# AV_Board.net
KiCad netlist of a schematic drawn in EAGLE
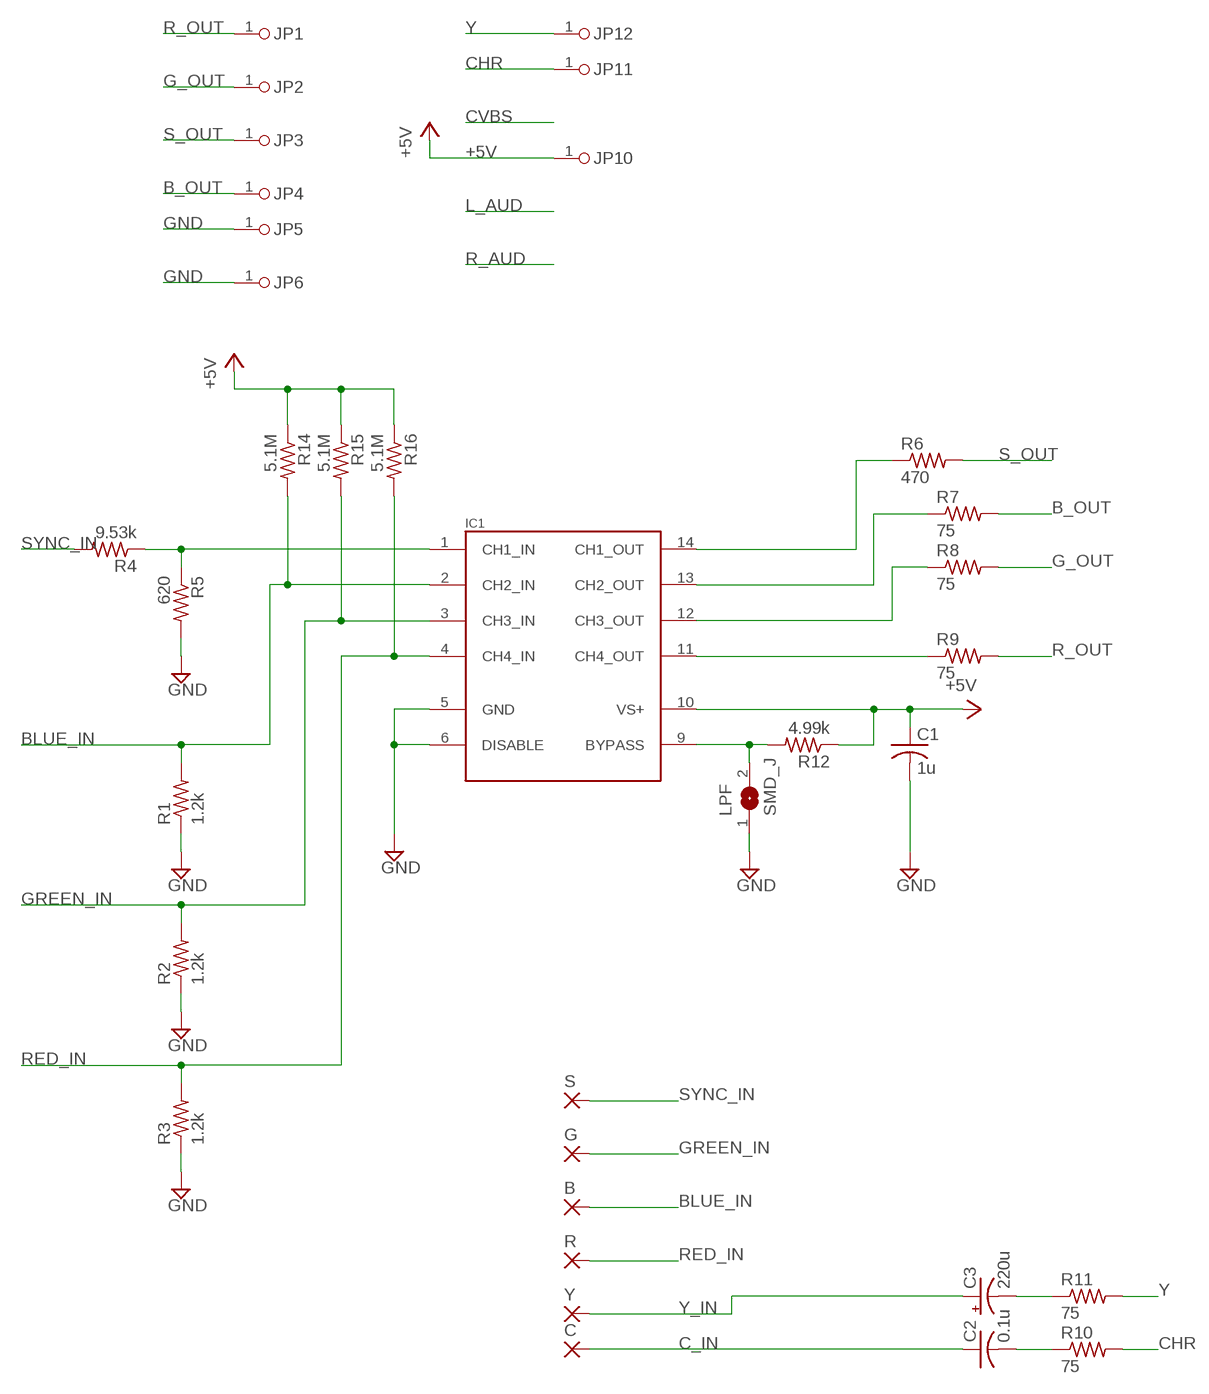
[diagram p0: schematic, sheet 1]

(export (version "E")
  (design (tool "Eeschema 10.0.6"))
  (components
    (comp (ref "B")
      (value "SMD2")
      (footprint "eagle-import:SMD1,27-2,54")
      (libsource (lib "eagle-import") (part "SMD2"))
    )
    (comp (ref "C")
      (value "SMD2")
      (footprint "eagle-import:SMD1,27-2,54")
      (libsource (lib "eagle-import") (part "SMD2"))
    )
    (comp (ref "C1")
      (value "1u")
      (footprint "eagle-import:C0603")
      (libsource (lib "eagle-import") (part "C-USC0603"))
    )
    (comp (ref "C2")
      (value "0.1u")
      (footprint "eagle-import:C0603")
      (libsource (lib "eagle-import") (part "C-USC0603"))
    )
    (comp (ref "C3")
      (value "220u")
      (footprint "eagle-import:CT6032")
      (libsource (lib "eagle-import") (part "CPOL-USCT6032"))
    )
    (comp (ref "G")
      (value "SMD2")
      (footprint "eagle-import:SMD1,27-2,54")
      (libsource (lib "eagle-import") (part "SMD2"))
    )
    (comp (ref "IC1")
      (value "THS7374IPWR")
      (footprint "eagle-import:TSSOP14")
      (libsource (lib "eagle-import") (part "THS7374IPWR"))
    )
    (comp (ref "JP1")
      (value "PINHD-1X1")
      (footprint "eagle-import:1X01")
      (libsource (lib "eagle-import") (part "PINHD-1X1"))
    )
    (comp (ref "JP2")
      (value "PINHD-1X1")
      (footprint "eagle-import:1X01")
      (libsource (lib "eagle-import") (part "PINHD-1X1"))
    )
    (comp (ref "JP3")
      (value "PINHD-1X1")
      (footprint "eagle-import:1X01")
      (libsource (lib "eagle-import") (part "PINHD-1X1"))
    )
    (comp (ref "JP4")
      (value "PINHD-1X1")
      (footprint "eagle-import:1X01")
      (libsource (lib "eagle-import") (part "PINHD-1X1"))
    )
    (comp (ref "JP5")
      (value "PINHD-1X1")
      (footprint "eagle-import:1X01")
      (libsource (lib "eagle-import") (part "PINHD-1X1"))
    )
    (comp (ref "JP6")
      (value "PINHD-1X1")
      (footprint "eagle-import:1X01")
      (libsource (lib "eagle-import") (part "PINHD-1X1"))
    )
    (comp (ref "JP10")
      (value "PINHD-1X1")
      (footprint "eagle-import:1X01")
      (libsource (lib "eagle-import") (part "PINHD-1X1"))
    )
    (comp (ref "JP11")
      (value "PINHD-1X1")
      (footprint "eagle-import:1X01")
      (libsource (lib "eagle-import") (part "PINHD-1X1"))
    )
    (comp (ref "JP12")
      (value "PINHD-1X1")
      (footprint "eagle-import:1X01")
      (libsource (lib "eagle-import") (part "PINHD-1X1"))
    )
    (comp (ref "LPF")
      (value "SMD_J")
      (footprint "eagle-import:SJ")
      (libsource (lib "eagle-import") (part "SMD_J"))
    )
    (comp (ref "R")
      (value "SMD2")
      (footprint "eagle-import:SMD1,27-2,54")
      (libsource (lib "eagle-import") (part "SMD2"))
    )
    (comp (ref "R1")
      (value "1.2k")
      (footprint "eagle-import:R0603")
      (libsource (lib "eagle-import") (part "R-US_R0603"))
    )
    (comp (ref "R2")
      (value "1.2k")
      (footprint "eagle-import:R0603")
      (libsource (lib "eagle-import") (part "R-US_R0603"))
    )
    (comp (ref "R3")
      (value "1.2k")
      (footprint "eagle-import:R0603")
      (libsource (lib "eagle-import") (part "R-US_R0603"))
    )
    (comp (ref "R4")
      (value "9.53k")
      (footprint "eagle-import:R0603")
      (libsource (lib "eagle-import") (part "R-US_R0603"))
    )
    (comp (ref "R5")
      (value "620")
      (footprint "eagle-import:R0603")
      (libsource (lib "eagle-import") (part "R-US_R0603"))
    )
    (comp (ref "R6")
      (value "470")
      (footprint "eagle-import:R0603")
      (libsource (lib "eagle-import") (part "R-US_R0603"))
    )
    (comp (ref "R7")
      (value "75")
      (footprint "eagle-import:R0603")
      (libsource (lib "eagle-import") (part "R-US_R0603"))
    )
    (comp (ref "R8")
      (value "75")
      (footprint "eagle-import:R0603")
      (libsource (lib "eagle-import") (part "R-US_R0603"))
    )
    (comp (ref "R9")
      (value "75")
      (footprint "eagle-import:R0603")
      (libsource (lib "eagle-import") (part "R-US_R0603"))
    )
    (comp (ref "R10")
      (value "75")
      (footprint "eagle-import:R0603")
      (libsource (lib "eagle-import") (part "R-US_R0603"))
    )
    (comp (ref "R11")
      (value "75")
      (footprint "eagle-import:R0603")
      (libsource (lib "eagle-import") (part "R-US_R0603"))
    )
    (comp (ref "R12")
      (value "4.99k")
      (footprint "eagle-import:R0603")
      (libsource (lib "eagle-import") (part "R-US_R0603"))
    )
    (comp (ref "R14")
      (value "5.1M")
      (footprint "eagle-import:R0603")
      (libsource (lib "eagle-import") (part "R-US_R0603"))
    )
    (comp (ref "R15")
      (value "5.1M")
      (footprint "eagle-import:R0603")
      (libsource (lib "eagle-import") (part "R-US_R0603"))
    )
    (comp (ref "R16")
      (value "5.1M")
      (footprint "eagle-import:R0603")
      (libsource (lib "eagle-import") (part "R-US_R0603"))
    )
    (comp (ref "S")
      (value "SMD2")
      (footprint "eagle-import:SMD1,27-2,54")
      (libsource (lib "eagle-import") (part "SMD2"))
    )
    (comp (ref "Y")
      (value "SMD2")
      (footprint "eagle-import:SMD1,27-2,54")
      (libsource (lib "eagle-import") (part "SMD2"))
    )
  )
  (nets
    (net (code "1") (name "+5V") (class "Default")
      (node (ref "C1") (pin "1") (pinfunction "1_1") (pintype "passive"))
      (node (ref "IC1") (pin "10") (pinfunction "VS+_10") (pintype "bidirectional"))
      (node (ref "JP10") (pin "1") (pinfunction "1_1") (pintype "passive"))
      (node (ref "R12") (pin "1") (pinfunction "1_1") (pintype "passive"))
      (node (ref "R14") (pin "1") (pinfunction "1_1") (pintype "passive"))
      (node (ref "R15") (pin "1") (pinfunction "1_1") (pintype "passive"))
      (node (ref "R16") (pin "1") (pinfunction "1_1") (pintype "passive"))
    )
    (net (code "2") (name "/BLUE_IN") (class "Default")
      (node (ref "B") (pin "1") (pinfunction "P_1") (pintype "passive"))
      (node (ref "IC1") (pin "2") (pinfunction "CH2_IN_2") (pintype "bidirectional"))
      (node (ref "R1") (pin "2") (pinfunction "2_2") (pintype "passive"))
      (node (ref "R14") (pin "2") (pinfunction "2_2") (pintype "passive"))
    )
    (net (code "3") (name "/B_OUT") (class "Default")
      (node (ref "JP4") (pin "1") (pinfunction "1_1") (pintype "passive"))
      (node (ref "R7") (pin "2") (pinfunction "2_2") (pintype "passive"))
    )
    (net (code "4") (name "/CHR") (class "Default")
      (node (ref "JP11") (pin "1") (pinfunction "1_1") (pintype "passive"))
      (node (ref "R10") (pin "2") (pinfunction "2_2") (pintype "passive"))
    )
    (net (code "6") (name "/C_IN") (class "Default")
      (node (ref "C") (pin "1") (pinfunction "P_1") (pintype "passive"))
      (node (ref "C2") (pin "1") (pinfunction "1_1") (pintype "passive"))
    )
    (net (code "7") (name "/GREEN_IN") (class "Default")
      (node (ref "G") (pin "1") (pinfunction "P_1") (pintype "passive"))
      (node (ref "IC1") (pin "3") (pinfunction "CH3_IN_3") (pintype "bidirectional"))
      (node (ref "R15") (pin "2") (pinfunction "2_2") (pintype "passive"))
      (node (ref "R2") (pin "2") (pinfunction "2_2") (pintype "passive"))
    )
    (net (code "8") (name "/G_OUT") (class "Default")
      (node (ref "JP2") (pin "1") (pinfunction "1_1") (pintype "passive"))
      (node (ref "R8") (pin "2") (pinfunction "2_2") (pintype "passive"))
    )
    (net (code "10") (name "/RED_IN") (class "Default")
      (node (ref "IC1") (pin "4") (pinfunction "CH4_IN_4") (pintype "bidirectional"))
      (node (ref "R") (pin "1") (pinfunction "P_1") (pintype "passive"))
      (node (ref "R16") (pin "2") (pinfunction "2_2") (pintype "passive"))
      (node (ref "R3") (pin "2") (pinfunction "2_2") (pintype "passive"))
    )
    (net (code "12") (name "/R_OUT") (class "Default")
      (node (ref "JP1") (pin "1") (pinfunction "1_1") (pintype "passive"))
      (node (ref "R9") (pin "2") (pinfunction "2_2") (pintype "passive"))
    )
    (net (code "13") (name "/SYNC_IN") (class "Default")
      (node (ref "R4") (pin "2") (pinfunction "2_2") (pintype "passive"))
      (node (ref "S") (pin "1") (pinfunction "P_1") (pintype "passive"))
    )
    (net (code "14") (name "/S_OUT") (class "Default")
      (node (ref "JP3") (pin "1") (pinfunction "1_1") (pintype "passive"))
      (node (ref "R6") (pin "2") (pinfunction "2_2") (pintype "passive"))
    )
    (net (code "15") (name "/Y") (class "Default")
      (node (ref "JP12") (pin "1") (pinfunction "1_1") (pintype "passive"))
      (node (ref "R11") (pin "2") (pinfunction "2_2") (pintype "passive"))
    )
    (net (code "16") (name "/Y_IN") (class "Default")
      (node (ref "C3") (pin "+") (pinfunction "+_+") (pintype "passive"))
      (node (ref "Y") (pin "1") (pinfunction "P_1") (pintype "passive"))
    )
    (net (code "17") (name "GND") (class "Default")
      (node (ref "C1") (pin "2") (pinfunction "2_2") (pintype "passive"))
      (node (ref "IC1") (pin "5") (pinfunction "GND_5") (pintype "bidirectional"))
      (node (ref "IC1") (pin "6") (pinfunction "DISABLE_6") (pintype "bidirectional"))
      (node (ref "JP5") (pin "1") (pinfunction "1_1") (pintype "passive"))
      (node (ref "JP6") (pin "1") (pinfunction "1_1") (pintype "passive"))
      (node (ref "LPF") (pin "1") (pinfunction "1_1") (pintype "passive"))
      (node (ref "R1") (pin "1") (pinfunction "1_1") (pintype "passive"))
      (node (ref "R2") (pin "1") (pinfunction "1_1") (pintype "passive"))
      (node (ref "R3") (pin "1") (pinfunction "1_1") (pintype "passive"))
      (node (ref "R5") (pin "2") (pinfunction "2_2") (pintype "passive"))
    )
    (net (code "18") (name "Net-(C2-Pad2)") (class "Default")
      (node (ref "C2") (pin "2") (pinfunction "2_2") (pintype "passive"))
      (node (ref "R10") (pin "1") (pinfunction "1_1") (pintype "passive"))
    )
    (net (code "19") (name "Net-(C3-Pad-)") (class "Default")
      (node (ref "C3") (pin "-") (pinfunction "-_-") (pintype "passive"))
      (node (ref "R11") (pin "1") (pinfunction "1_1") (pintype "passive"))
    )
    (net (code "20") (name "Net-(IC1-BYPASS)") (class "Default")
      (node (ref "IC1") (pin "9") (pinfunction "BYPASS_9") (pintype "bidirectional"))
      (node (ref "LPF") (pin "2") (pinfunction "2_2") (pintype "passive"))
      (node (ref "R12") (pin "2") (pinfunction "2_2") (pintype "passive"))
    )
    (net (code "21") (name "Net-(IC1-CH1_IN)") (class "Default")
      (node (ref "IC1") (pin "1") (pinfunction "CH1_IN_1") (pintype "bidirectional"))
      (node (ref "R4") (pin "1") (pinfunction "1_1") (pintype "passive"))
      (node (ref "R5") (pin "1") (pinfunction "1_1") (pintype "passive"))
    )
    (net (code "22") (name "Net-(IC1-CH1_OUT)") (class "Default")
      (node (ref "IC1") (pin "14") (pinfunction "CH1_OUT_14") (pintype "bidirectional"))
      (node (ref "R6") (pin "1") (pinfunction "1_1") (pintype "passive"))
    )
    (net (code "23") (name "Net-(IC1-CH2_OUT)") (class "Default")
      (node (ref "IC1") (pin "13") (pinfunction "CH2_OUT_13") (pintype "bidirectional"))
      (node (ref "R7") (pin "1") (pinfunction "1_1") (pintype "passive"))
    )
    (net (code "24") (name "Net-(IC1-CH3_OUT)") (class "Default")
      (node (ref "IC1") (pin "12") (pinfunction "CH3_OUT_12") (pintype "bidirectional"))
      (node (ref "R8") (pin "1") (pinfunction "1_1") (pintype "passive"))
    )
    (net (code "25") (name "Net-(IC1-CH4_OUT)") (class "Default")
      (node (ref "IC1") (pin "11") (pinfunction "CH4_OUT_11") (pintype "bidirectional"))
      (node (ref "R9") (pin "1") (pinfunction "1_1") (pintype "passive"))
    )
  )
)
